# Interface.net
KiCad netlist of a schematic drawn in Altium Designer
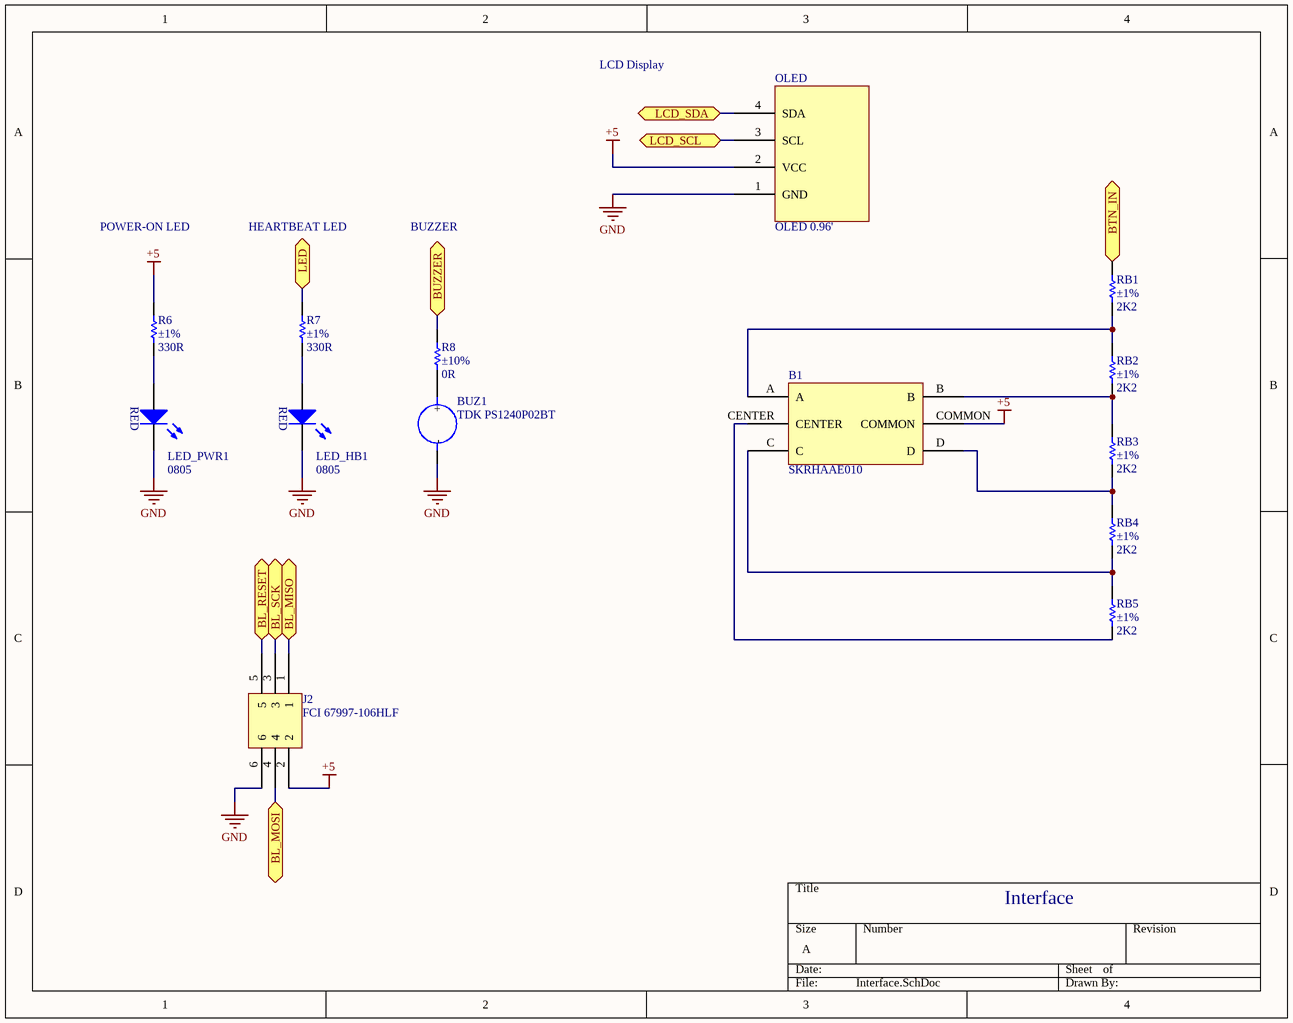
[diagram p0: Interface.SchDoc]

(export (version "E")
  (design (tool "Eeschema 10.0.6"))
  (components
    (comp (ref "B1")
      (value "SKRHAAE010")
      (footprint "PCB-uddfpa39w3pawwu0f32n-1")
      (description "TACT switch 4-direction with Center-Push Function (Surface Mount)")
      (libsource (lib "CommunityVault") (part "SYM-0t5k0v9upau5edea4oo5-1"))
    )
    (comp (ref "BUZ1")
      (value "TDK PS1240P02BT")
      (footprint "2P-7.6-D12X6.5H")
      (description "Audio Indicator Buzzer Piezo 3Vo-p Pin Through Hole")
      (fields (field (name "MANUFACTURER PART NUMBER") "PS1240P02BT"))
      (libsource (lib "Octopart library") (part "TDK-PS1240P02BT-2"))
    )
    (comp (ref "J2")
      (value "FCI 67997-106HLF")
      (footprint "PCB-94q9r8plw7fzhg0k9c12-1")
      (description "Conn; Rect; Header; Unshrouded; 6 Pos; 2.54mm Pitch; 2-Row; Thru-Hole; BergStik")
      (fields (field (name "MANUFACTURER PART NUMBER") "67997-106HLF"))
      (libsource (lib "CommunityVault") (part "CMP-c8f30399bb8b1734-1"))
    )
    (comp (ref "LED_HB1")
      (value "CMP-7f15b6173d91a0d2-5")
      (footprint "LED0805")
      (description "LED; SMD; 0805; red; 7.2-17mcd; 2x1.25mm; 170°; 1.8÷2.6V; 20mA")
      (fields (field (name "CASE/PACKAGE") "0805") (field (name "MANUFACTURER PART NUMBER") "HSMH-C170"))
      (libsource (lib "CommunityVault") (part "CMP-7f15b6173d91a0d2-5"))
    )
    (comp (ref "LED_PWR1")
      (value "CMP-7f15b6173d91a0d2-5")
      (footprint "LED0805")
      (description "LED; SMD; 0805; red; 7.2-17mcd; 2x1.25mm; 170°; 1.8÷2.6V; 20mA")
      (fields (field (name "CASE/PACKAGE") "0805") (field (name "MANUFACTURER PART NUMBER") "HSMH-C170"))
      (libsource (lib "CommunityVault") (part "CMP-7f15b6173d91a0d2-5"))
    )
    (comp (ref "OLED")
      (value "OLED 0.96'")
      (footprint "PCBComponent_1 - duplicate")
      (description "0.96' oled i2c screen")
      (libsource (lib "FavoritesLibrary") (part "SYM-am4xhbx8j6fw9q56sa5u-1"))
    )
    (comp (ref "R6")
      (value "Bourns CR0805-FX-4701GLF")
      (footprint "PCB-4097432-1")
      (description "Res Thick Film 0805 4.7K Ohm 1% 1/8W ±100ppm/°C Molded SMD SMD Paper Tape on Plastic Reel")
      (fields
        (field (name "MANUFACTURER PART NUMBER") "CR0805-FX-4701GLF")
        (field (name "RESISTANCE TOLERANCE") "±1%")
        (field (name "RESISTANCE") "330R")
      )
      (libsource (lib "CommunityVault") (part "CMP-97505e06006c4897-1"))
    )
    (comp (ref "R7")
      (value "Bourns CR0805-FX-4701GLF")
      (footprint "PCB-4097432-1")
      (description "Res Thick Film 0805 4.7K Ohm 1% 1/8W ±100ppm/°C Molded SMD SMD Paper Tape on Plastic Reel")
      (fields
        (field (name "MANUFACTURER PART NUMBER") "CR0805-FX-4701GLF")
        (field (name "RESISTANCE TOLERANCE") "±1%")
        (field (name "RESISTANCE") "330R")
      )
      (libsource (lib "CommunityVault") (part "CMP-97505e06006c4897-1"))
    )
    (comp (ref "R8")
      (value "Bourns CR0805-FX-4701GLF")
      (footprint "PCB-4097432-1")
      (description "Res Thick Film 0805 4.7K Ohm 1% 1/8W ±100ppm/°C Molded SMD SMD Paper Tape on Plastic Reel")
      (fields
        (field (name "MANUFACTURER PART NUMBER") "CR0805-FX-4701GLF")
        (field (name "RESISTANCE TOLERANCE") "±10%")
        (field (name "RESISTANCE") "0R")
      )
      (libsource (lib "CommunityVault") (part "CMP-97505e06006c4897-1"))
    )
    (comp (ref "RB1")
      (value "Bourns CR0805-FX-4701GLF")
      (footprint "PCB-4097432-1")
      (description "Res Thick Film 0805 4.7K Ohm 1% 1/8W ±100ppm/°C Molded SMD SMD Paper Tape on Plastic Reel")
      (fields
        (field (name "MANUFACTURER PART NUMBER") "CR0805-FX-4701GLF")
        (field (name "RESISTANCE TOLERANCE") "±1%")
        (field (name "RESISTANCE") "2K2")
      )
      (libsource (lib "CommunityVault") (part "CMP-97505e06006c4897-1"))
    )
    (comp (ref "RB2")
      (value "Bourns CR0805-FX-4701GLF")
      (footprint "PCB-4097432-1")
      (description "Res Thick Film 0805 4.7K Ohm 1% 1/8W ±100ppm/°C Molded SMD SMD Paper Tape on Plastic Reel")
      (fields
        (field (name "MANUFACTURER PART NUMBER") "CR0805-FX-4701GLF")
        (field (name "RESISTANCE TOLERANCE") "±1%")
        (field (name "RESISTANCE") "2K2")
      )
      (libsource (lib "CommunityVault") (part "CMP-97505e06006c4897-1"))
    )
    (comp (ref "RB3")
      (value "Bourns CR0805-FX-4701GLF")
      (footprint "PCB-4097432-1")
      (description "Res Thick Film 0805 4.7K Ohm 1% 1/8W ±100ppm/°C Molded SMD SMD Paper Tape on Plastic Reel")
      (fields
        (field (name "MANUFACTURER PART NUMBER") "CR0805-FX-4701GLF")
        (field (name "RESISTANCE TOLERANCE") "±1%")
        (field (name "RESISTANCE") "2K2")
      )
      (libsource (lib "CommunityVault") (part "CMP-97505e06006c4897-1"))
    )
    (comp (ref "RB4")
      (value "Bourns CR0805-FX-4701GLF")
      (footprint "PCB-4097432-1")
      (description "Res Thick Film 0805 4.7K Ohm 1% 1/8W ±100ppm/°C Molded SMD SMD Paper Tape on Plastic Reel")
      (fields
        (field (name "MANUFACTURER PART NUMBER") "CR0805-FX-4701GLF")
        (field (name "RESISTANCE TOLERANCE") "±1%")
        (field (name "RESISTANCE") "2K2")
      )
      (libsource (lib "CommunityVault") (part "CMP-97505e06006c4897-1"))
    )
    (comp (ref "RB5")
      (value "Bourns CR0805-FX-4701GLF")
      (footprint "PCB-4097432-1")
      (description "Res Thick Film 0805 4.7K Ohm 1% 1/8W ±100ppm/°C Molded SMD SMD Paper Tape on Plastic Reel")
      (fields
        (field (name "MANUFACTURER PART NUMBER") "CR0805-FX-4701GLF")
        (field (name "RESISTANCE TOLERANCE") "±1%")
        (field (name "RESISTANCE") "2K2")
      )
      (libsource (lib "CommunityVault") (part "CMP-97505e06006c4897-1"))
    )
  )
  (nets
    (net (code "1") (name "+5") (class "Default")
      (node (ref "B1") (pin "COMMON") (pinfunction "COMMON_COMMON") (pintype "passive"))
      (node (ref "J2") (pin "2") (pinfunction "2_2") (pintype "passive"))
      (node (ref "OLED") (pin "2") (pinfunction "VCC_2") (pintype "passive"))
      (node (ref "R6") (pin "2") (pinfunction "2_2") (pintype "passive"))
    )
    (net (code "2") (name "/BL_MISO") (class "Default")
      (node (ref "J2") (pin "1") (pinfunction "1_1") (pintype "passive"))
    )
    (net (code "3") (name "/BL_MOSI") (class "Default")
      (node (ref "J2") (pin "4") (pinfunction "4_4") (pintype "passive"))
    )
    (net (code "4") (name "/BL_RESET") (class "Default")
      (node (ref "J2") (pin "5") (pinfunction "5_5") (pintype "passive"))
    )
    (net (code "5") (name "/BL_SCK") (class "Default")
      (node (ref "J2") (pin "3") (pinfunction "3_3") (pintype "passive"))
    )
    (net (code "6") (name "/BTN_IN") (class "Default")
      (node (ref "RB1") (pin "2") (pinfunction "2_2") (pintype "passive"))
    )
    (net (code "7") (name "/BUZZER") (class "Default")
      (node (ref "R8") (pin "2") (pinfunction "2_2") (pintype "passive"))
    )
    (net (code "8") (name "/LCD_SCL") (class "Default")
      (node (ref "OLED") (pin "3") (pinfunction "SCL_3") (pintype "passive"))
    )
    (net (code "9") (name "/LCD_SDA") (class "Default")
      (node (ref "OLED") (pin "4") (pinfunction "SDA_4") (pintype "passive"))
    )
    (net (code "10") (name "/LED") (class "Default")
      (node (ref "R7") (pin "2") (pinfunction "2_2") (pintype "passive"))
    )
    (net (code "11") (name "GND") (class "Default")
      (node (ref "BUZ1") (pin "-") (pinfunction "-_-") (pintype "passive"))
      (node (ref "J2") (pin "6") (pinfunction "6_6") (pintype "passive"))
      (node (ref "LED_HB1") (pin "1") (pinfunction "K_1") (pintype "passive"))
      (node (ref "LED_PWR1") (pin "1") (pinfunction "K_1") (pintype "passive"))
      (node (ref "OLED") (pin "1") (pinfunction "GND_1") (pintype "passive"))
    )
    (net (code "12") (name "Net-(B1-PadA)") (class "Default")
      (node (ref "B1") (pin "A") (pinfunction "A_A") (pintype "passive"))
      (node (ref "RB1") (pin "1") (pinfunction "1_1") (pintype "passive"))
      (node (ref "RB2") (pin "2") (pinfunction "2_2") (pintype "passive"))
    )
    (net (code "13") (name "Net-(B1-PadB)") (class "Default")
      (node (ref "B1") (pin "B") (pinfunction "B_B") (pintype "passive"))
      (node (ref "RB2") (pin "1") (pinfunction "1_1") (pintype "passive"))
      (node (ref "RB3") (pin "2") (pinfunction "2_2") (pintype "passive"))
    )
    (net (code "14") (name "Net-(B1-PadC)") (class "Default")
      (node (ref "B1") (pin "C") (pinfunction "C_C") (pintype "passive"))
      (node (ref "RB4") (pin "1") (pinfunction "1_1") (pintype "passive"))
      (node (ref "RB5") (pin "2") (pinfunction "2_2") (pintype "passive"))
    )
    (net (code "15") (name "Net-(B1-PadCENTER)") (class "Default")
      (node (ref "B1") (pin "CENTER") (pinfunction "CENTER_CENTER") (pintype "passive"))
      (node (ref "RB5") (pin "1") (pinfunction "1_1") (pintype "passive"))
    )
    (net (code "16") (name "Net-(B1-PadD)") (class "Default")
      (node (ref "B1") (pin "D") (pinfunction "D_D") (pintype "passive"))
      (node (ref "RB3") (pin "1") (pinfunction "1_1") (pintype "passive"))
      (node (ref "RB4") (pin "2") (pinfunction "2_2") (pintype "passive"))
    )
    (net (code "17") (name "Net-(BUZ1-Pad+)") (class "Default")
      (node (ref "BUZ1") (pin "+") (pinfunction "+_+") (pintype "passive"))
      (node (ref "R8") (pin "1") (pinfunction "1_1") (pintype "passive"))
    )
    (net (code "18") (name "Net-(LED_HB1-A)") (class "Default")
      (node (ref "LED_HB1") (pin "2") (pinfunction "A_2") (pintype "passive"))
      (node (ref "R7") (pin "1") (pinfunction "1_1") (pintype "passive"))
    )
    (net (code "19") (name "Net-(LED_PWR1-A)") (class "Default")
      (node (ref "LED_PWR1") (pin "2") (pinfunction "A_2") (pintype "passive"))
      (node (ref "R6") (pin "1") (pinfunction "1_1") (pintype "passive"))
    )
  )
)
